# Motor_Driver.net
KiCad netlist of a schematic drawn in Altium Designer
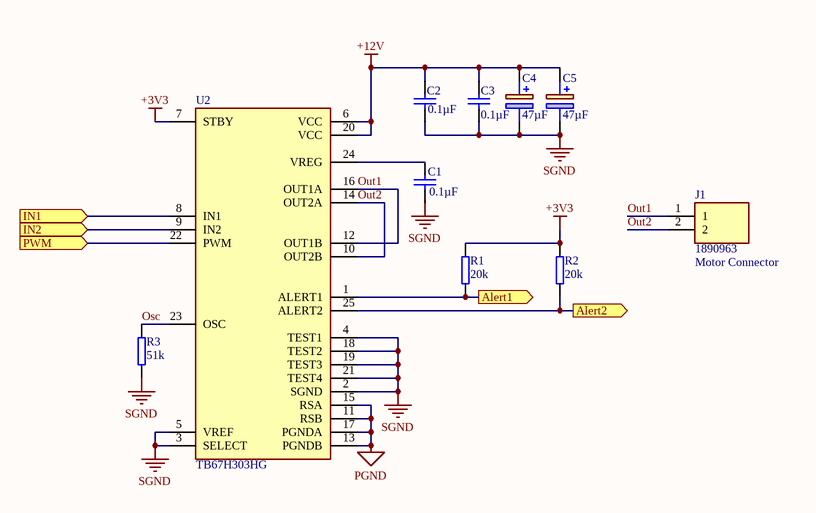
[diagram p0: Motor_Driver.SchDoc]

(export (version "E")
  (design (tool "Eeschema 10.0.6"))
  (components
    (comp (ref "C1")
      (value "0.1µF")
      (footprint "Capacitor 0603")
      (description "Capacitor")
      (libsource (lib "Schematic_Lib") (part "Capacitor 0603"))
    )
    (comp (ref "C2")
      (value "0.1µF")
      (footprint "Capacitor 0603")
      (description "Capacitor")
      (libsource (lib "Schematic_Lib") (part "Capacitor 0603"))
    )
    (comp (ref "C3")
      (value "0.1µF")
      (footprint "Capacitor 0603")
      (description "Capacitor")
      (libsource (lib "Schematic_Lib") (part "Capacitor 0603"))
    )
    (comp (ref "C4")
      (value "47µF")
      (footprint "CAPAE660X550N")
      (fields
        (field (name "MOUSER PART NUMBER") "710-865080543009")
        (field (name "MANUFACTURER_PART_NUMBER") "865080543009")
      )
      (libsource (lib "Schematic_Lib") (part "865080543009"))
    )
    (comp (ref "C5")
      (value "47µF")
      (footprint "CAPAE660X550N")
      (fields
        (field (name "MOUSER PART NUMBER") "710-865080543009")
        (field (name "MANUFACTURER_PART_NUMBER") "865080543009")
      )
      (libsource (lib "Schematic_Lib") (part "865080543009"))
    )
    (comp (ref "J1")
      (value "1890963")
      (footprint "1890963")
      (description "Connector: 2pin screw terminal")
      (fields (field (name "MOUSER PART NUMBER") "651-1890963"))
      (libsource (lib "Schematic_Lib") (part "1890963"))
    )
    (comp (ref "R1")
      (value "20k")
      (footprint "Resistor 0603")
      (description "Resistor")
      (libsource (lib "Schematic_Lib") (part "Resistor 0603"))
    )
    (comp (ref "R2")
      (value "20k")
      (footprint "Resistor 0603")
      (description "Resistor")
      (libsource (lib "Schematic_Lib") (part "Resistor 0603"))
    )
    (comp (ref "R3")
      (value "51k")
      (footprint "Resistor 0603")
      (description "Resistor")
      (libsource (lib "Schematic_Lib") (part "Resistor 0603"))
    )
    (comp (ref "U2")
      (value "TB67H303HG")
      (footprint "TO100P2930X465X1937-25")
      (description "Full Bridge")
      (libsource (lib "Schematic_Lib") (part "TB67H303HG"))
    )
  )
  (nets
    (net (code "1") (name "+3V3") (class "Default")
      (node (ref "R1") (pin "2") (pintype "passive"))
      (node (ref "R2") (pin "2") (pintype "passive"))
      (node (ref "U2") (pin "7") (pinfunction "STBY_7") (pintype "passive"))
    )
    (net (code "2") (name "+12V") (class "Default")
      (node (ref "C2") (pin "1") (pinfunction "1_1") (pintype "passive"))
      (node (ref "C3") (pin "1") (pinfunction "1_1") (pintype "passive"))
      (node (ref "C4") (pin "1") (pinfunction "+_1") (pintype "passive"))
      (node (ref "C5") (pin "1") (pinfunction "+_1") (pintype "passive"))
      (node (ref "U2") (pin "20") (pinfunction "VCC_20") (pintype "passive"))
      (node (ref "U2") (pin "6") (pinfunction "VCC_6") (pintype "passive"))
    )
    (net (code "3") (name "/Alert1") (class "Default")
      (node (ref "R1") (pin "1") (pintype "passive"))
      (node (ref "U2") (pin "1") (pinfunction "ALERT1_1") (pintype "passive"))
    )
    (net (code "4") (name "/Alert2") (class "Default")
      (node (ref "R2") (pin "1") (pintype "passive"))
      (node (ref "U2") (pin "25") (pinfunction "ALERT2_25") (pintype "passive"))
    )
    (net (code "5") (name "/IN1") (class "Default")
      (node (ref "U2") (pin "8") (pinfunction "IN1_8") (pintype "passive"))
    )
    (net (code "6") (name "/IN2") (class "Default")
      (node (ref "U2") (pin "9") (pinfunction "IN2_9") (pintype "passive"))
    )
    (net (code "7") (name "/Osc") (class "Default")
      (node (ref "R3") (pin "2") (pintype "passive"))
      (node (ref "U2") (pin "23") (pinfunction "OSC_23") (pintype "passive"))
    )
    (net (code "8") (name "/Out1") (class "Default")
      (node (ref "J1") (pin "1") (pinfunction "1_1") (pintype "passive"))
      (node (ref "U2") (pin "12") (pinfunction "OUT1B_12") (pintype "passive"))
      (node (ref "U2") (pin "16") (pinfunction "OUT1A_16") (pintype "passive"))
    )
    (net (code "9") (name "/Out2") (class "Default")
      (node (ref "J1") (pin "2") (pinfunction "2_2") (pintype "passive"))
      (node (ref "U2") (pin "10") (pinfunction "OUT2B_10") (pintype "passive"))
      (node (ref "U2") (pin "14") (pinfunction "OUT2A_14") (pintype "passive"))
    )
    (net (code "10") (name "/PWM") (class "Default")
      (node (ref "U2") (pin "22") (pinfunction "PWM_22") (pintype "passive"))
    )
    (net (code "11") (name "Net-(U2-VREG)") (class "Default")
      (node (ref "C1") (pin "1") (pinfunction "1_1") (pintype "passive"))
      (node (ref "U2") (pin "24") (pinfunction "VREG_24") (pintype "passive"))
    )
    (net (code "12") (name "PGND") (class "Default")
      (node (ref "U2") (pin "11") (pinfunction "RSB_11") (pintype "passive"))
      (node (ref "U2") (pin "13") (pinfunction "PGNDB_13") (pintype "passive"))
      (node (ref "U2") (pin "15") (pinfunction "RSA_15") (pintype "passive"))
      (node (ref "U2") (pin "17") (pinfunction "PGNDA_17") (pintype "passive"))
    )
    (net (code "13") (name "SGND") (class "Default")
      (node (ref "C1") (pin "2") (pinfunction "2_2") (pintype "passive"))
      (node (ref "C2") (pin "2") (pinfunction "2_2") (pintype "passive"))
      (node (ref "C3") (pin "2") (pinfunction "2_2") (pintype "passive"))
      (node (ref "C4") (pin "2") (pinfunction "-_2") (pintype "passive"))
      (node (ref "C5") (pin "2") (pinfunction "-_2") (pintype "passive"))
      (node (ref "R3") (pin "1") (pintype "passive"))
      (node (ref "U2") (pin "18") (pinfunction "TEST2_18") (pintype "passive"))
      (node (ref "U2") (pin "19") (pinfunction "TEST3_19") (pintype "passive"))
      (node (ref "U2") (pin "2") (pinfunction "SGND_2") (pintype "passive"))
      (node (ref "U2") (pin "21") (pinfunction "TEST4_21") (pintype "passive"))
      (node (ref "U2") (pin "3") (pinfunction "SELECT_3") (pintype "passive"))
      (node (ref "U2") (pin "4") (pinfunction "TEST1_4") (pintype "passive"))
      (node (ref "U2") (pin "5") (pinfunction "VREF_5") (pintype "passive"))
    )
  )
)
